# RadioModule.net
KiCad netlist of a schematic drawn in Altium Designer
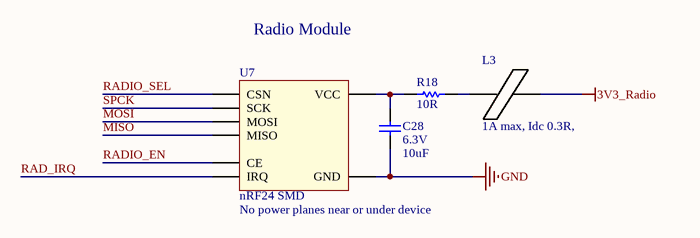
[diagram p0: RadioModule.SchDoc]

(export (version "E")
  (design (tool "Eeschema 10.0.6"))
  (components
    (comp (ref "C28")
      (value "10uF")
      (footprint "CAPC1608L")
      (description "CAP CER 10UF X5R +-20% 6V3 0603")
      (fields (field (name "VOLTAGE - RATED") "6.3V"))
      (libsource (lib "ECE AD19Components_19V1") (part "CC_10uF_0603"))
    )
    (comp (ref "L3")
      (value "1A max, Idc 0.3R,")
      (footprint "INDC3216L")
      (description "Ferrite Bead, Rdc 0.3R, Z100MHZ 600R, Imax 1A, SMD 1206")
      (fields
        (field (name "MANUFACTURER") "FAIR-RITE")
        (field (name "MANUFACTURER PART NUMBER") "2512066017Y1")
      )
      (libsource (lib "ECE AD19Components_19V1") (part "IN_Ferrite-Bead"))
    )
    (comp (ref "R18")
      (value "10R")
      (footprint "RESC1608L")
      (description "RES 10 OHM 1/10W 5% 0603 SMD")
      (libsource (lib "ECE AD19Components_19V1") (part "RS_10R"))
    )
    (comp (ref "U7")
      (value "nRF24 SMD")
      (footprint "NRF24")
      (description "nRF24 SMD Module")
      (fields (field (name "WARNING") "No power planes near or under device"))
      (libsource (lib "ENCE461AD19_19V2") (part "NRF24"))
    )
  )
  (nets
    (net (code "1") (name "/MISO") (class "Default")
      (node (ref "U7") (pin "7") (pinfunction "MISO_7") (pintype "passive"))
    )
    (net (code "2") (name "/MOSI") (class "Default")
      (node (ref "U7") (pin "6") (pinfunction "MOSI_6") (pintype "passive"))
    )
    (net (code "3") (name "/RADIO_EN") (class "Default")
      (node (ref "U7") (pin "3") (pinfunction "CE_3") (pintype "passive"))
    )
    (net (code "4") (name "/RADIO_SEL") (class "Default")
      (node (ref "U7") (pin "4") (pinfunction "CSN_4") (pintype "passive"))
    )
    (net (code "5") (name "/RAD_IRQ") (class "Default")
      (node (ref "U7") (pin "8") (pinfunction "IRQ_8") (pintype "passive"))
    )
    (net (code "6") (name "/SPCK") (class "Default")
      (node (ref "U7") (pin "5") (pinfunction "SCK_5") (pintype "passive"))
    )
    (net (code "7") (name "3V3_Radio") (class "Default")
      (node (ref "L3") (pin "2") (pinfunction "2_2") (pintype "passive"))
    )
    (net (code "8") (name "GND") (class "Default")
      (node (ref "C28") (pin "1") (pinfunction "1_1") (pintype "passive"))
      (node (ref "U7") (pin "2") (pinfunction "GND_2") (pintype "passive"))
    )
    (net (code "9") (name "Net-(L3-Pad1)") (class "Default")
      (node (ref "L3") (pin "1") (pinfunction "1_1") (pintype "passive"))
      (node (ref "R18") (pin "2") (pinfunction "2_2") (pintype "passive"))
    )
    (net (code "10") (name "Net-(U7-VCC)") (class "Default")
      (node (ref "C28") (pin "2") (pinfunction "2_2") (pintype "passive"))
      (node (ref "R18") (pin "1") (pinfunction "1_1") (pintype "passive"))
      (node (ref "U7") (pin "1") (pinfunction "VCC_1") (pintype "passive"))
    )
  )
)
